# Sheet1.net
KiCad netlist of a schematic drawn in Altium Designer
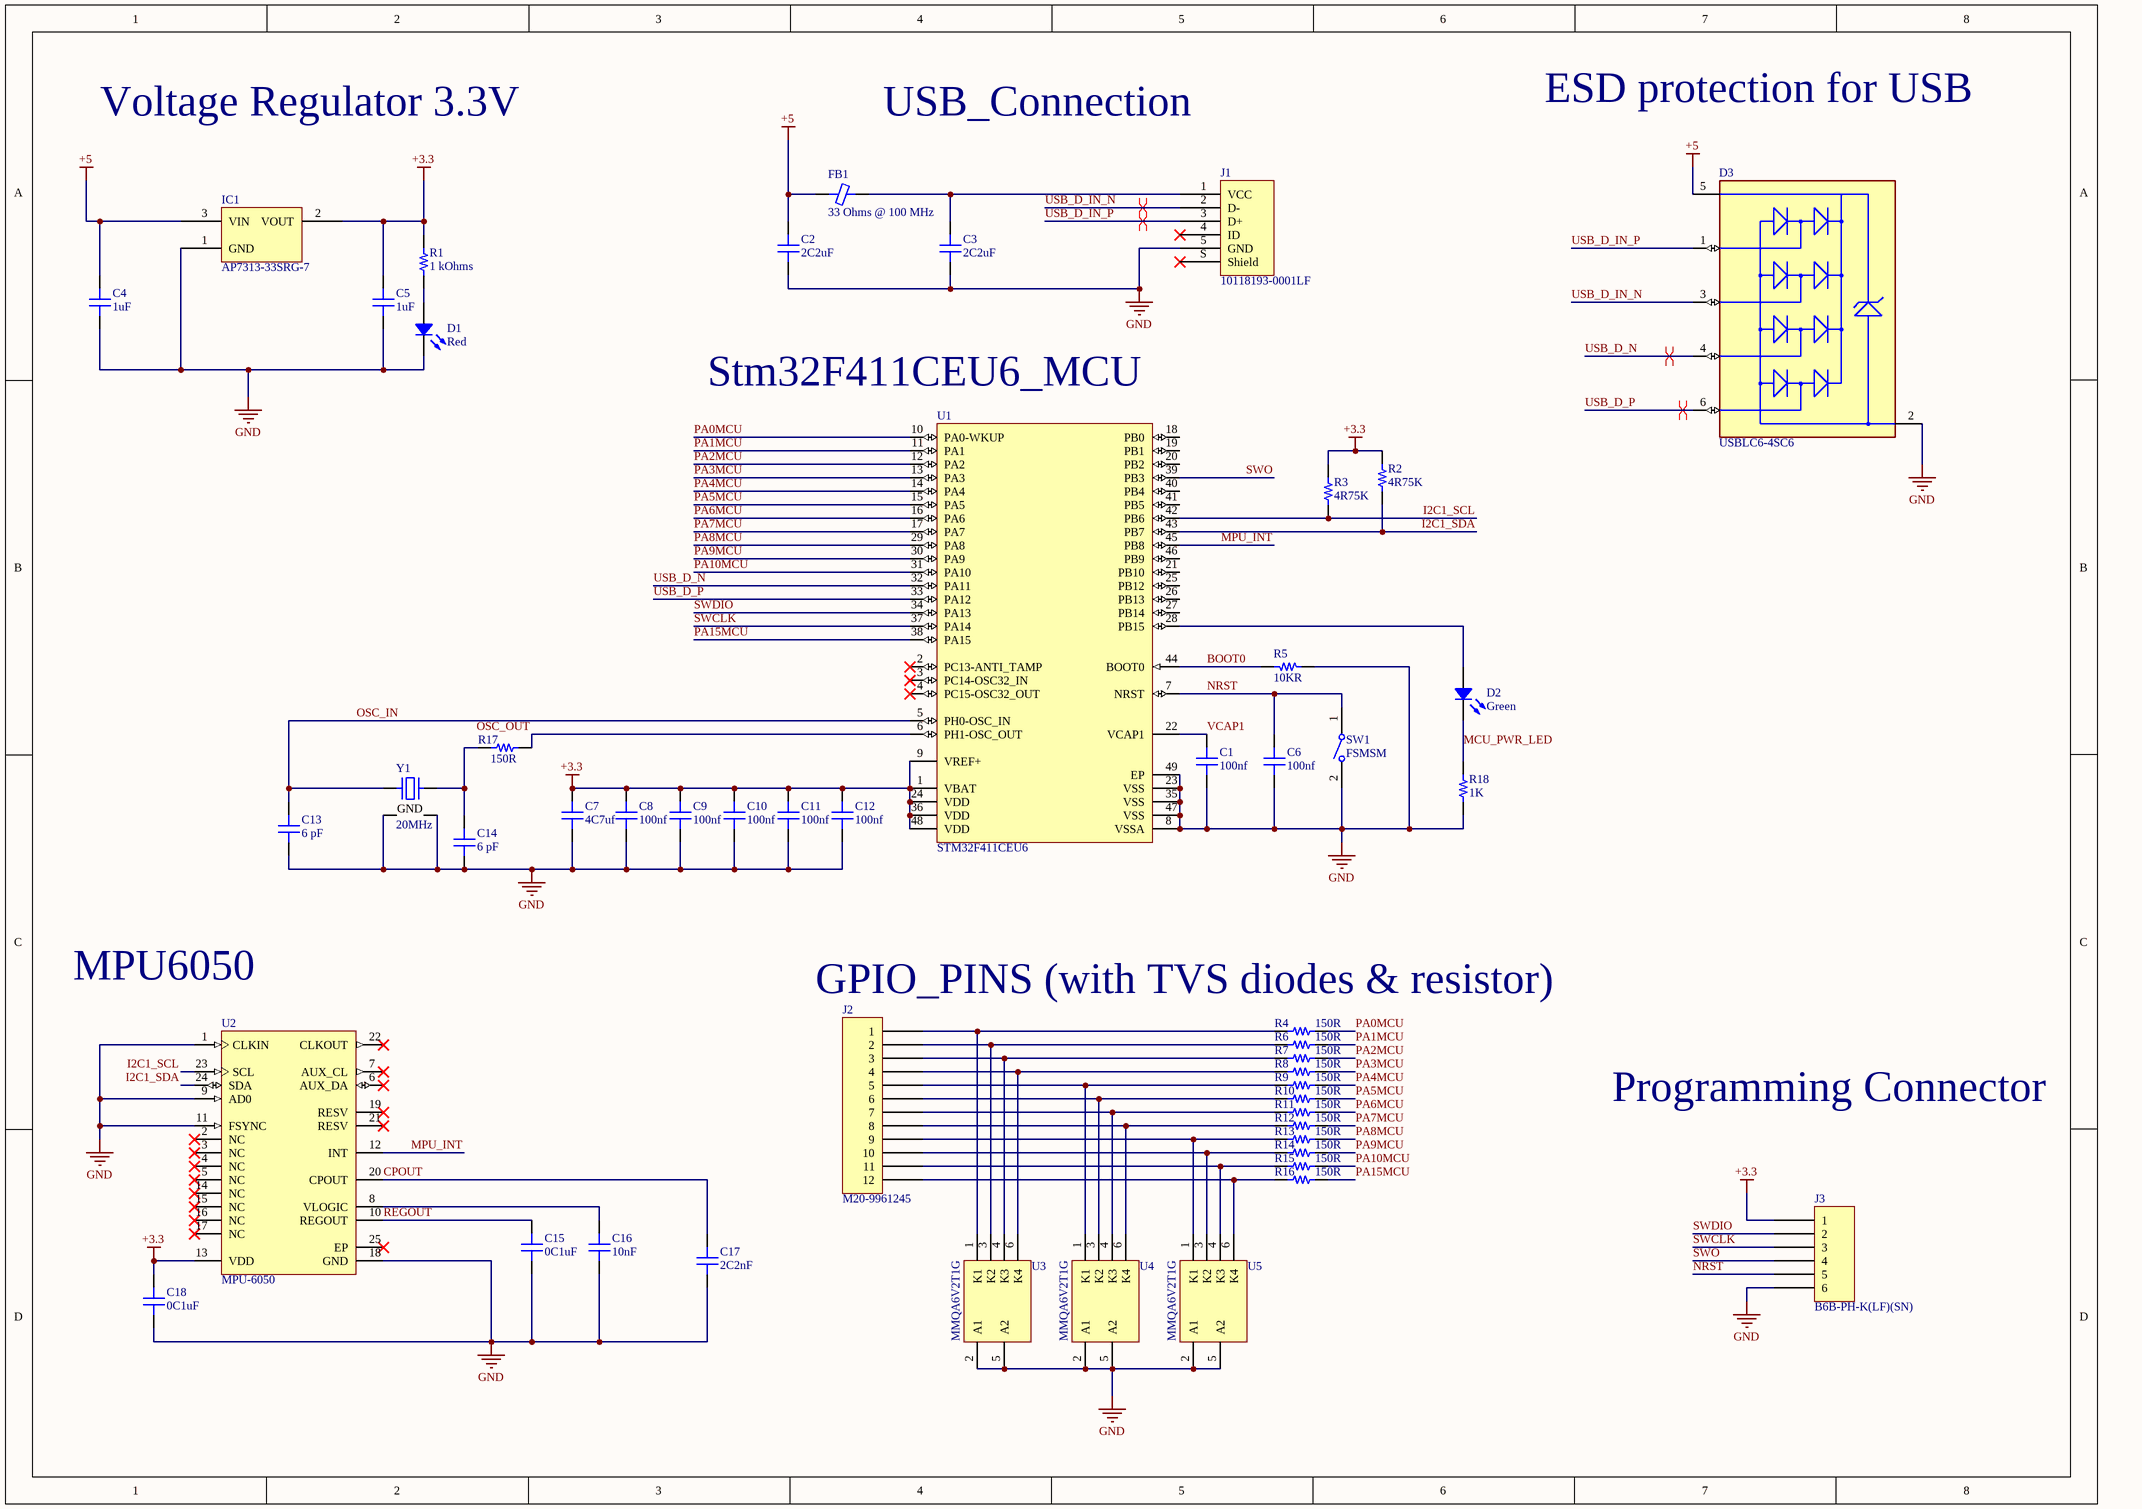
[diagram p0: Sheet1.SchDoc]

(export (version "E")
  (design (tool "Eeschema 10.0.6"))
  (components
    (comp (ref "C1")
      (value "100nf")
      (footprint "CAP 0603_1608")
      (description "CAP CER 0.1UF 6.3V X7R 0603")
      (fields
        (field (name "PART NUMBER") "6R3X14W104MV4T")
        (field (name "MANUFACTURER") "Johanson Dielectrics Inc.")
      )
      (libsource (lib "Celestial Altium Library - altium_library") (part "Capacitor"))
    )
    (comp (ref "C2")
      (value "2C2uF")
      (footprint "CAP 0805_2012")
      (description "CAP CER 2.2UF 16V X5R 0805")
      (fields (field (name "PART NUMBER") "EMK212BJ225KGHT") (field (name "MANUFACTURER") "Taiyo Yuden"))
      (libsource (lib "Celestial Altium Library - altium_library") (part "Capacitor"))
    )
    (comp (ref "C3")
      (value "2C2uF")
      (footprint "CAP 0805_2012")
      (description "CAP CER 2.2UF 16V X5R 0805")
      (fields (field (name "PART NUMBER") "EMK212BJ225KGHT") (field (name "MANUFACTURER") "Taiyo Yuden"))
      (libsource (lib "Celestial Altium Library - altium_library") (part "Capacitor"))
    )
    (comp (ref "C4")
      (value "1uF")
      (footprint "CAP 0805_2012")
      (description "CAP CER 0805 1UF 16V X7R 10%")
      (fields (field (name "PART NUMBER") "C0805C105K4RECAUTO") (field (name "MANUFACTURER") "KEMET"))
      (libsource (lib "Celestial Altium Library - altium_library") (part "Capacitor"))
    )
    (comp (ref "C5")
      (value "1uF")
      (footprint "CAP 0805_2012")
      (description "CAP CER 0805 1UF 16V X7R 10%")
      (fields (field (name "PART NUMBER") "C0805C105K4RECAUTO") (field (name "MANUFACTURER") "KEMET"))
      (libsource (lib "Celestial Altium Library - altium_library") (part "Capacitor"))
    )
    (comp (ref "C6")
      (value "100nf")
      (footprint "CAP 0603_1608")
      (description "CAP CER 0.1UF 6.3V X7R 0603")
      (fields
        (field (name "PART NUMBER") "6R3X14W104MV4T")
        (field (name "MANUFACTURER") "Johanson Dielectrics Inc.")
      )
      (libsource (lib "Celestial Altium Library - altium_library") (part "Capacitor"))
    )
    (comp (ref "C7")
      (value "4C7uf")
      (footprint "CAP 0603_1608")
      (description "CAP CER 4.7UF 6.3V X5R 0603")
      (fields (field (name "PART NUMBER") "06036D475KAT4A") (field (name "MANUFACTURER") "AVX Corporation"))
      (libsource (lib "Celestial Altium Library - altium_library") (part "Capacitor"))
    )
    (comp (ref "C8")
      (value "100nf")
      (footprint "CAP 0603_1608")
      (description "CAP CER 0.1UF 6.3V X7R 0603")
      (fields
        (field (name "PART NUMBER") "6R3X14W104MV4T")
        (field (name "MANUFACTURER") "Johanson Dielectrics Inc.")
      )
      (libsource (lib "Celestial Altium Library - altium_library") (part "Capacitor"))
    )
    (comp (ref "C9")
      (value "100nf")
      (footprint "CAP 0603_1608")
      (description "CAP CER 0.1UF 6.3V X7R 0603")
      (fields
        (field (name "PART NUMBER") "6R3X14W104MV4T")
        (field (name "MANUFACTURER") "Johanson Dielectrics Inc.")
      )
      (libsource (lib "Celestial Altium Library - altium_library") (part "Capacitor"))
    )
    (comp (ref "C10")
      (value "100nf")
      (footprint "CAP 0603_1608")
      (description "CAP CER 0.1UF 6.3V X7R 0603")
      (fields
        (field (name "PART NUMBER") "6R3X14W104MV4T")
        (field (name "MANUFACTURER") "Johanson Dielectrics Inc.")
      )
      (libsource (lib "Celestial Altium Library - altium_library") (part "Capacitor"))
    )
    (comp (ref "C11")
      (value "100nf")
      (footprint "CAP 0603_1608")
      (description "CAP CER 0.1UF 6.3V X7R 0603")
      (fields
        (field (name "PART NUMBER") "6R3X14W104MV4T")
        (field (name "MANUFACTURER") "Johanson Dielectrics Inc.")
      )
      (libsource (lib "Celestial Altium Library - altium_library") (part "Capacitor"))
    )
    (comp (ref "C12")
      (value "100nf")
      (footprint "CAP 0603_1608")
      (description "CAP CER 0.1UF 6.3V X7R 0603")
      (fields
        (field (name "PART NUMBER") "6R3X14W104MV4T")
        (field (name "MANUFACTURER") "Johanson Dielectrics Inc.")
      )
      (libsource (lib "Celestial Altium Library - altium_library") (part "Capacitor"))
    )
    (comp (ref "C13")
      (value "6 pF")
      (footprint "CAP 0805_2012")
      (description "CAP CER 6PF 50V C0G/NPO 0805")
      (fields (field (name "PART NUMBER") "CC0805CRNPO9BN6R0") (field (name "MANUFACTURER") "Yageo"))
      (libsource (lib "Celestial Altium Library - altium_library") (part "Capacitor"))
    )
    (comp (ref "C14")
      (value "6 pF")
      (footprint "CAP 0805_2012")
      (description "CAP CER 6PF 50V C0G/NPO 0805")
      (fields (field (name "PART NUMBER") "CC0805CRNPO9BN6R0") (field (name "MANUFACTURER") "Yageo"))
      (libsource (lib "Celestial Altium Library - altium_library") (part "Capacitor"))
    )
    (comp (ref "C15")
      (value "0C1uF")
      (footprint "CAP 0603_1608")
      (description "CAP CER 0.1UF 10V X7R 0603")
      (fields (field (name "PART NUMBER") "C0603X104K8RAC7867") (field (name "MANUFACTURER") "KEMET"))
      (libsource (lib "Celestial Altium Library - altium_library") (part "Capacitor"))
    )
    (comp (ref "C16")
      (value "10nF")
      (footprint "CAP 0805_2012")
      (description "CAP CER 10000PF 10V X7R 0805")
      (fields (field (name "PART NUMBER") "0805ZC103KAT2A") (field (name "MANUFACTURER") "AVX Corporation"))
      (libsource (lib "Celestial Altium Library - altium_library") (part "Capacitor"))
    )
    (comp (ref "C17")
      (value "2C2nF")
      (footprint "CAP 0603_1608")
      (description "CAP CER 2200PF 50V X7R 0603")
      (fields (field (name "PART NUMBER") "C0603X222K5RACAUTO") (field (name "MANUFACTURER") "KEMET"))
      (libsource (lib "Celestial Altium Library - altium_library") (part "Capacitor"))
    )
    (comp (ref "C18")
      (value "0C1uF")
      (footprint "CAP 0603_1608")
      (description "CAP CER 0.1UF 10V X7R 0603")
      (fields (field (name "PART NUMBER") "C0603X104K8RAC7867") (field (name "MANUFACTURER") "KEMET"))
      (libsource (lib "Celestial Altium Library - altium_library") (part "Capacitor"))
    )
    (comp (ref "D1")
      (value "Red")
      (footprint "LED 0603_1608 RED")
      (description "WL-SMCW SMT MONO-COLOR CHIP LED")
      (fields (field (name "PART NUMBER") "150060RS86000") (field (name "MANUFACTURER") "Würth Elektronik"))
      (libsource (lib "Celestial Altium Library - altium_library") (part "LED"))
    )
    (comp (ref "D2")
      (value "Green")
      (footprint "LED 0603_1608 GREEN")
      (description "WL-SMCW SMT MONO-COLOR CHIP LED")
      (fields (field (name "PART NUMBER") "150060VS75020") (field (name "MANUFACTURER") "Würth Elektronik"))
      (libsource (lib "Celestial Altium Library - altium_library") (part "LED"))
    )
    (comp (ref "D3")
      (value "USBLC6-4SC6")
      (footprint "FP-SOT23-6L-MFG")
      (description "TVS DIODE 5.25V 17V SOT23-6")
      (fields
        (field (name "MANUFACTURER") "STMicroelectronics")
        (field (name "OCTOPART") "https://octopart.com/usblc6-4sc6-stmicroelectronics-347147")
      )
      (libsource (lib "Altium Content Vault") (part "3e70b616ccdc4c88b528e1820c4a7da"))
    )
    (comp (ref "FB1")
      (value "33 Ohms @ 100 MHz")
      (footprint "FER 0201_0603")
      (description "FERRITE BEAD 33 OHM 0201 1LN")
      (fields (field (name "PART NUMBER") "MMZ0603F330CT000") (field (name "MANUFACTURER") "TDK Corporation"))
      (libsource (lib "Celestial Altium Library - altium_library") (part "Ferrite Chip"))
    )
    (comp (ref "IC1")
      (value "AP7313-33SRG-7")
      (footprint "DIODES SOT-23-3")
      (description "IC REG LIN 3.3V 150MA SOT23R-3")
      (fields (field (name "MANUFACTURER") "Diodes Incorporated"))
      (libsource (lib "Celestial Altium Library - altium_library") (part "Diodes Inc AP7313R"))
    )
    (comp (ref "J1")
      (value "10118193-0001LF")
      (footprint "FCI USB 10118193-0001LF")
      (description "CONN RCPT USB2.0 MICRO B SMD R/A")
      (fields (field (name "MANUFACTURER") "Amphenol ICC (FCI)"))
      (libsource (lib "Celestial Altium Library - altium_library") (part "USB 2.0 Type B Micro"))
    )
    (comp (ref "J2")
      (value "M20-9961245")
      (footprint "HARWIN M20-9961245")
      (description "CONN HEADER R/A 12POS 2.54MM")
      (fields (field (name "MANUFACTURER") "Harwin Inc."))
      (libsource (lib "Celestial Altium Library - altium_library") (part "12 Pin"))
    )
    (comp (ref "J3")
      (value "B6B-PH-K(LF)(SN)")
      (footprint "JST B6B-PH-K")
      (description "CONN HEADER VERT 6POS 2MM")
      (fields (field (name "MANUFACTURER") "JST Sales America Inc."))
      (libsource (lib "Celestial Altium Library - altium_library") (part "6 Pin"))
    )
    (comp (ref "R1")
      (value "1 kOhms")
      (footprint "RES 0805_2012")
      (description "3430 A2 1% 1K0 100PPM 1K RL")
      (fields
        (field (name "PART NUMBER") "3430A2F1K0TDF")
        (field (name "MANUFACTURER") "TE Connectivity Passive Product")
      )
      (libsource (lib "Celestial Altium Library - altium_library") (part "Resistor"))
    )
    (comp (ref "R2")
      (value "4R75K")
      (footprint "RES 0402_1005")
      (description "RES 4.75 KOHMS 0.1% 1/16W 0402")
      (fields
        (field (name "PART NUMBER") "RQ73C1E4K75BTD")
        (field (name "MANUFACTURER") "TE Connectivity Passive Product")
      )
      (libsource (lib "Celestial Altium Library - altium_library") (part "Resistor"))
    )
    (comp (ref "R3")
      (value "4R75K")
      (footprint "RES 0402_1005")
      (description "RES 4.75 KOHMS 0.1% 1/16W 0402")
      (fields
        (field (name "PART NUMBER") "RQ73C1E4K75BTD")
        (field (name "MANUFACTURER") "TE Connectivity Passive Product")
      )
      (libsource (lib "Celestial Altium Library - altium_library") (part "Resistor"))
    )
    (comp (ref "R4")
      (value "150R")
      (footprint "RES 0603_1608")
      (description "RA73F 1J 150R 0.1% 5K RL")
      (fields
        (field (name "PART NUMBER") "RA73F1J150RBTD")
        (field (name "MANUFACTURER") "TE Connectivity Passive Product")
      )
      (libsource (lib "Celestial Altium Library - altium_library") (part "Resistor"))
    )
    (comp (ref "R5")
      (value "10KR")
      (footprint "RES 0603_1608")
      (description "RES 10K OHM 0.5% 1/3W 0603")
      (fields
        (field (name "PART NUMBER") "SG73G1JTTD1002D")
        (field (name "MANUFACTURER") "KOA Speer Electronics, Inc.")
      )
      (libsource (lib "Celestial Altium Library - altium_library") (part "Resistor"))
    )
    (comp (ref "R6")
      (value "150R")
      (footprint "RES 0603_1608")
      (description "RA73F 1J 150R 0.1% 5K RL")
      (fields
        (field (name "PART NUMBER") "RA73F1J150RBTD")
        (field (name "MANUFACTURER") "TE Connectivity Passive Product")
      )
      (libsource (lib "Celestial Altium Library - altium_library") (part "Resistor"))
    )
    (comp (ref "R7")
      (value "150R")
      (footprint "RES 0603_1608")
      (description "RA73F 1J 150R 0.1% 5K RL")
      (fields
        (field (name "PART NUMBER") "RA73F1J150RBTD")
        (field (name "MANUFACTURER") "TE Connectivity Passive Product")
      )
      (libsource (lib "Celestial Altium Library - altium_library") (part "Resistor"))
    )
    (comp (ref "R8")
      (value "150R")
      (footprint "RES 0603_1608")
      (description "RA73F 1J 150R 0.1% 5K RL")
      (fields
        (field (name "PART NUMBER") "RA73F1J150RBTD")
        (field (name "MANUFACTURER") "TE Connectivity Passive Product")
      )
      (libsource (lib "Celestial Altium Library - altium_library") (part "Resistor"))
    )
    (comp (ref "R9")
      (value "150R")
      (footprint "RES 0603_1608")
      (description "RA73F 1J 150R 0.1% 5K RL")
      (fields
        (field (name "PART NUMBER") "RA73F1J150RBTD")
        (field (name "MANUFACTURER") "TE Connectivity Passive Product")
      )
      (libsource (lib "Celestial Altium Library - altium_library") (part "Resistor"))
    )
    (comp (ref "R10")
      (value "150R")
      (footprint "RES 0603_1608")
      (description "RA73F 1J 150R 0.1% 5K RL")
      (fields
        (field (name "PART NUMBER") "RA73F1J150RBTD")
        (field (name "MANUFACTURER") "TE Connectivity Passive Product")
      )
      (libsource (lib "Celestial Altium Library - altium_library") (part "Resistor"))
    )
    (comp (ref "R11")
      (value "150R")
      (footprint "RES 0603_1608")
      (description "RA73F 1J 150R 0.1% 5K RL")
      (fields
        (field (name "PART NUMBER") "RA73F1J150RBTD")
        (field (name "MANUFACTURER") "TE Connectivity Passive Product")
      )
      (libsource (lib "Celestial Altium Library - altium_library") (part "Resistor"))
    )
    (comp (ref "R12")
      (value "150R")
      (footprint "RES 0603_1608")
      (description "RA73F 1J 150R 0.1% 5K RL")
      (fields
        (field (name "PART NUMBER") "RA73F1J150RBTD")
        (field (name "MANUFACTURER") "TE Connectivity Passive Product")
      )
      (libsource (lib "Celestial Altium Library - altium_library") (part "Resistor"))
    )
    (comp (ref "R13")
      (value "150R")
      (footprint "RES 0603_1608")
      (description "RA73F 1J 150R 0.1% 5K RL")
      (fields
        (field (name "PART NUMBER") "RA73F1J150RBTD")
        (field (name "MANUFACTURER") "TE Connectivity Passive Product")
      )
      (libsource (lib "Celestial Altium Library - altium_library") (part "Resistor"))
    )
    (comp (ref "R14")
      (value "150R")
      (footprint "RES 0603_1608")
      (description "RA73F 1J 150R 0.1% 5K RL")
      (fields
        (field (name "PART NUMBER") "RA73F1J150RBTD")
        (field (name "MANUFACTURER") "TE Connectivity Passive Product")
      )
      (libsource (lib "Celestial Altium Library - altium_library") (part "Resistor"))
    )
    (comp (ref "R15")
      (value "150R")
      (footprint "RES 0603_1608")
      (description "RA73F 1J 150R 0.1% 5K RL")
      (fields
        (field (name "PART NUMBER") "RA73F1J150RBTD")
        (field (name "MANUFACTURER") "TE Connectivity Passive Product")
      )
      (libsource (lib "Celestial Altium Library - altium_library") (part "Resistor"))
    )
    (comp (ref "R16")
      (value "150R")
      (footprint "RES 0603_1608")
      (description "RA73F 1J 150R 0.1% 5K RL")
      (fields
        (field (name "PART NUMBER") "RA73F1J150RBTD")
        (field (name "MANUFACTURER") "TE Connectivity Passive Product")
      )
      (libsource (lib "Celestial Altium Library - altium_library") (part "Resistor"))
    )
    (comp (ref "R17")
      (value "150R")
      (footprint "RES 0402_1005")
      (description "RES 150 OHM 1% 1/4W 0402")
      (fields
        (field (name "PART NUMBER") "ERJ-PA2F1500X")
        (field (name "MANUFACTURER") "Panasonic Electronic Components")
      )
      (libsource (lib "Celestial Altium Library - altium_library") (part "Resistor"))
    )
    (comp (ref "R18")
      (value "1K")
      (footprint "RES 0402_1005")
      (description "0402 ANTI-SULFUR RES. , 0.5%, 1K")
      (fields
        (field (name "PART NUMBER") "ERJ-U02D1001X")
        (field (name "MANUFACTURER") "Panasonic Electronic Components")
      )
      (libsource (lib "Celestial Altium Library - altium_library") (part "Resistor"))
    )
    (comp (ref "SW1")
      (value "FSMSM")
      (footprint "TECO-FSMSM-2_V")
      (description "FSMSM Push Button Switch, 50 mA, -35 to 85 degC, 2-Pin SMD, RoHS, Bulk")
      (fields (field (name "MANUFACTURER") "TE Connectivity"))
      (libsource (lib "Altium Content Vault") (part "SW-SPST-2_C"))
    )
    (comp (ref "U1")
      (value "STM32F411CEU6")
      (footprint "STM-UFQFPN48_L")
      (libsource (lib "Altium Content Vault") (part "MC-ARM-STM32F411-UFQFPN48"))
    )
    (comp (ref "U2")
      (value "MPU-6050")
      (footprint "IS-QFN-24_V")
      (fields (field (name "MANUFACTURER") "InvenSense"))
      (libsource (lib "Altium Content Vault") (part "IS-MPU-6050-QFN-24"))
    )
    (comp (ref "U3")
      (value "MMQA6V2T1G")
      (footprint "ONSC-SC-74-6-318F-05_V")
      (fields (field (name "MANUFACTURER") "On Semiconductor"))
      (libsource (lib "Altium Content Vault") (part "ONSC-K1A2K3K4A5K6-6"))
    )
    (comp (ref "U4")
      (value "MMQA6V2T1G")
      (footprint "ONSC-SC-74-6-318F-05_V")
      (fields (field (name "MANUFACTURER") "On Semiconductor"))
      (libsource (lib "Altium Content Vault") (part "ONSC-K1A2K3K4A5K6-6"))
    )
    (comp (ref "U5")
      (value "MMQA6V2T1G")
      (footprint "ONSC-SC-74-6-318F-05_V")
      (fields (field (name "MANUFACTURER") "On Semiconductor"))
      (libsource (lib "Altium Content Vault") (part "ONSC-K1A2K3K4A5K6-6"))
    )
    (comp (ref "Y1")
      (value "20MHz")
      (footprint "KYOCERA CX2016DB")
      (description "CRYSTAL 20.0000MHZ 8PF SMD")
      (fields
        (field (name "PART NUMBER") "CX2016DB20000D0FLJCC")
        (field (name "MANUFACTURER") "Kyocera International Inc. Electronic Components")
      )
      (libsource (lib "Celestial Altium Library - altium_library") (part "Kyocera Crystal CX2016DB"))
    )
  )
  (nets
    (net (code "1") (name "+3.3") (class "Default")
      (node (ref "C10") (pin "1") (pinfunction "1_1") (pintype "passive"))
      (node (ref "C11") (pin "1") (pinfunction "1_1") (pintype "passive"))
      (node (ref "C12") (pin "1") (pinfunction "1_1") (pintype "passive"))
      (node (ref "C18") (pin "1") (pinfunction "1_1") (pintype "passive"))
      (node (ref "C5") (pin "1") (pinfunction "1_1") (pintype "passive"))
      (node (ref "C7") (pin "1") (pinfunction "1_1") (pintype "passive"))
      (node (ref "C8") (pin "1") (pinfunction "1_1") (pintype "passive"))
      (node (ref "C9") (pin "1") (pinfunction "1_1") (pintype "passive"))
      (node (ref "IC1") (pin "2") (pinfunction "VOUT_2") (pintype "passive"))
      (node (ref "J3") (pin "1") (pinfunction "1_1") (pintype "passive"))
      (node (ref "R1") (pin "1") (pinfunction "1_1") (pintype "passive"))
      (node (ref "R2") (pin "1") (pinfunction "1_1") (pintype "passive"))
      (node (ref "R3") (pin "1") (pinfunction "1_1") (pintype "passive"))
      (node (ref "U1") (pin "1") (pinfunction "VBAT_1") (pintype "power_in"))
      (node (ref "U1") (pin "24") (pinfunction "VDD_24") (pintype "power_in"))
      (node (ref "U1") (pin "36") (pinfunction "VDD_36") (pintype "power_in"))
      (node (ref "U1") (pin "48") (pinfunction "VDD_48") (pintype "power_in"))
      (node (ref "U1") (pin "9") (pinfunction "VREF+_9") (pintype "power_in"))
      (node (ref "U2") (pin "13") (pinfunction "VDD_13") (pintype "power_in"))
    )
    (net (code "2") (name "+5") (class "Default")
      (node (ref "C2") (pin "2") (pinfunction "2_2") (pintype "passive"))
      (node (ref "C4") (pin "1") (pinfunction "1_1") (pintype "passive"))
      (node (ref "D3") (pin "5") (pinfunction "VBUS_5") (pintype "power_in"))
      (node (ref "FB1") (pin "1") (pinfunction "1_1") (pintype "passive"))
      (node (ref "IC1") (pin "3") (pinfunction "VIN_3") (pintype "passive"))
    )
    (net (code "3") (name "/BOOT0") (class "Default")
      (node (ref "R5") (pin "2") (pinfunction "2_2") (pintype "passive"))
      (node (ref "U1") (pin "44") (pinfunction "BOOT0_44") (pintype "input"))
    )
    (net (code "4") (name "/CPOUT") (class "Default")
      (node (ref "C17") (pin "1") (pinfunction "1_1") (pintype "passive"))
      (node (ref "U2") (pin "20") (pinfunction "CPOUT_20") (pintype "passive"))
    )
    (net (code "5") (name "/I2C1_SCL") (class "Default")
      (node (ref "R3") (pin "2") (pinfunction "2_2") (pintype "passive"))
      (node (ref "U1") (pin "42") (pinfunction "PB6_42") (pintype "bidirectional"))
      (node (ref "U2") (pin "23") (pinfunction "SCL_23") (pintype "input"))
    )
    (net (code "6") (name "/I2C1_SDA") (class "Default")
      (node (ref "R2") (pin "2") (pinfunction "2_2") (pintype "passive"))
      (node (ref "U1") (pin "43") (pinfunction "PB7_43") (pintype "bidirectional"))
      (node (ref "U2") (pin "24") (pinfunction "SDA_24") (pintype "bidirectional"))
    )
    (net (code "7") (name "/MCU_PWR_LED") (class "Default")
      (node (ref "D2") (pin "2") (pinfunction "2_2") (pintype "passive"))
      (node (ref "R18") (pin "1") (pinfunction "1_1") (pintype "passive"))
    )
    (net (code "8") (name "/MPU_INT") (class "Default")
      (node (ref "U1") (pin "45") (pinfunction "PB8_45") (pintype "bidirectional"))
      (node (ref "U2") (pin "12") (pinfunction "INT_12") (pintype "open_collector"))
    )
    (net (code "9") (name "/NRST") (class "Default")
      (node (ref "C6") (pin "1") (pinfunction "1_1") (pintype "passive"))
      (node (ref "J3") (pin "5") (pinfunction "5_5") (pintype "passive"))
      (node (ref "SW1") (pin "1") (pinfunction "1_1") (pintype "passive"))
      (node (ref "U1") (pin "7") (pinfunction "NRST_7") (pintype "bidirectional"))
    )
    (net (code "10") (name "/OSC_IN") (class "Default")
      (node (ref "C13") (pin "1") (pinfunction "1_1") (pintype "passive"))
      (node (ref "U1") (pin "5") (pinfunction "PH0-OSC_IN_5") (pintype "bidirectional"))
      (node (ref "Y1") (pin "1") (pinfunction "1_1") (pintype "passive"))
    )
    (net (code "11") (name "/OSC_OUT") (class "Default")
      (node (ref "R17") (pin "2") (pinfunction "2_2") (pintype "passive"))
      (node (ref "U1") (pin "6") (pinfunction "PH1-OSC_OUT_6") (pintype "bidirectional"))
    )
    (net (code "12") (name "/PA0MCU") (class "Default")
      (node (ref "R4") (pin "2") (pinfunction "2_2") (pintype "passive"))
      (node (ref "U1") (pin "10") (pinfunction "PA0-WKUP_10") (pintype "bidirectional"))
    )
    (net (code "13") (name "/PA1MCU") (class "Default")
      (node (ref "R6") (pin "2") (pinfunction "2_2") (pintype "passive"))
      (node (ref "U1") (pin "11") (pinfunction "PA1_11") (pintype "bidirectional"))
    )
    (net (code "14") (name "/PA2MCU") (class "Default")
      (node (ref "R7") (pin "2") (pinfunction "2_2") (pintype "passive"))
      (node (ref "U1") (pin "12") (pinfunction "PA2_12") (pintype "bidirectional"))
    )
    (net (code "15") (name "/PA3MCU") (class "Default")
      (node (ref "R8") (pin "2") (pinfunction "2_2") (pintype "passive"))
      (node (ref "U1") (pin "13") (pinfunction "PA3_13") (pintype "bidirectional"))
    )
    (net (code "16") (name "/PA4MCU") (class "Default")
      (node (ref "R9") (pin "2") (pinfunction "2_2") (pintype "passive"))
      (node (ref "U1") (pin "14") (pinfunction "PA4_14") (pintype "bidirectional"))
    )
    (net (code "17") (name "/PA5MCU") (class "Default")
      (node (ref "R10") (pin "2") (pinfunction "2_2") (pintype "passive"))
      (node (ref "U1") (pin "15") (pinfunction "PA5_15") (pintype "bidirectional"))
    )
    (net (code "18") (name "/PA6MCU") (class "Default")
      (node (ref "R11") (pin "2") (pinfunction "2_2") (pintype "passive"))
      (node (ref "U1") (pin "16") (pinfunction "PA6_16") (pintype "bidirectional"))
    )
    (net (code "19") (name "/PA7MCU") (class "Default")
      (node (ref "R12") (pin "2") (pinfunction "2_2") (pintype "passive"))
      (node (ref "U1") (pin "17") (pinfunction "PA7_17") (pintype "bidirectional"))
    )
    (net (code "20") (name "/PA8MCU") (class "Default")
      (node (ref "R13") (pin "2") (pinfunction "2_2") (pintype "passive"))
      (node (ref "U1") (pin "29") (pinfunction "PA8_29") (pintype "bidirectional"))
    )
    (net (code "21") (name "/PA9MCU") (class "Default")
      (node (ref "R14") (pin "2") (pinfunction "2_2") (pintype "passive"))
      (node (ref "U1") (pin "30") (pinfunction "PA9_30") (pintype "bidirectional"))
    )
    (net (code "22") (name "/PA10MCU") (class "Default")
      (node (ref "R15") (pin "2") (pinfunction "2_2") (pintype "passive"))
      (node (ref "U1") (pin "31") (pinfunction "PA10_31") (pintype "bidirectional"))
    )
    (net (code "23") (name "/PA15MCU") (class "Default")
      (node (ref "R16") (pin "2") (pinfunction "2_2") (pintype "passive"))
      (node (ref "U1") (pin "38") (pinfunction "PA15_38") (pintype "bidirectional"))
    )
    (net (code "24") (name "/REGOUT") (class "Default")
      (node (ref "C15") (pin "1") (pinfunction "1_1") (pintype "passive"))
      (node (ref "U2") (pin "10") (pinfunction "REGOUT_10") (pintype "passive"))
    )
    (net (code "25") (name "/SWCLK") (class "Default")
      (node (ref "J3") (pin "3") (pinfunction "3_3") (pintype "passive"))
      (node (ref "U1") (pin "37") (pinfunction "PA14_37") (pintype "bidirectional"))
    )
    (net (code "26") (name "/SWDIO") (class "Default")
      (node (ref "J3") (pin "2") (pinfunction "2_2") (pintype "passive"))
      (node (ref "U1") (pin "34") (pinfunction "PA13_34") (pintype "bidirectional"))
    )
    (net (code "27") (name "/SWO") (class "Default")
      (node (ref "J3") (pin "4") (pinfunction "4_4") (pintype "passive"))
      (node (ref "U1") (pin "39") (pinfunction "PB3_39") (pintype "bidirectional"))
    )
    (net (code "28") (name "/USB_D_IN_N") (class "Default")
      (node (ref "D3") (pin "3") (pinfunction "I/O2_3") (pintype "bidirectional"))
      (node (ref "J1") (pin "2") (pinfunction "D-_2") (pintype "passive"))
    )
    (net (code "29") (name "/USB_D_IN_P") (class "Default")
      (node (ref "D3") (pin "1") (pinfunction "I/O1_1") (pintype "bidirectional"))
      (node (ref "J1") (pin "3") (pinfunction "D+_3") (pintype "passive"))
    )
    (net (code "30") (name "/USB_D_N") (class "Default")
      (node (ref "D3") (pin "4") (pinfunction "I/O3_4") (pintype "bidirectional"))
      (node (ref "U1") (pin "32") (pinfunction "PA11_32") (pintype "bidirectional"))
    )
    (net (code "31") (name "/USB_D_P") (class "Default")
      (node (ref "D3") (pin "6") (pinfunction "I/O4_6") (pintype "bidirectional"))
      (node (ref "U1") (pin "33") (pinfunction "PA12_33") (pintype "bidirectional"))
    )
    (net (code "32") (name "/VCAP1") (class "Default")
      (node (ref "C1") (pin "1") (pinfunction "1_1") (pintype "passive"))
      (node (ref "U1") (pin "22") (pinfunction "VCAP1_22") (pintype "passive"))
    )
    (net (code "33") (name "GND") (class "Default")
      (node (ref "C1") (pin "2") (pinfunction "2_2") (pintype "passive"))
      (node (ref "C10") (pin "2") (pinfunction "2_2") (pintype "passive"))
      (node (ref "C11") (pin "2") (pinfunction "2_2") (pintype "passive"))
      (node (ref "C12") (pin "2") (pinfunction "2_2") (pintype "passive"))
      (node (ref "C13") (pin "2") (pinfunction "2_2") (pintype "passive"))
      (node (ref "C14") (pin "2") (pinfunction "2_2") (pintype "passive"))
      (node (ref "C15") (pin "2") (pinfunction "2_2") (pintype "passive"))
      (node (ref "C16") (pin "2") (pinfunction "2_2") (pintype "passive"))
      (node (ref "C17") (pin "2") (pinfunction "2_2") (pintype "passive"))
      (node (ref "C18") (pin "2") (pinfunction "2_2") (pintype "passive"))
      (node (ref "C2") (pin "1") (pinfunction "1_1") (pintype "passive"))
      (node (ref "C3") (pin "1") (pinfunction "1_1") (pintype "passive"))
      (node (ref "C4") (pin "2") (pinfunction "2_2") (pintype "passive"))
      (node (ref "C5") (pin "2") (pinfunction "2_2") (pintype "passive"))
      (node (ref "C6") (pin "2") (pinfunction "2_2") (pintype "passive"))
      (node (ref "C7") (pin "2") (pinfunction "2_2") (pintype "passive"))
      (node (ref "C8") (pin "2") (pinfunction "2_2") (pintype "passive"))
      (node (ref "C9") (pin "2") (pinfunction "2_2") (pintype "passive"))
      (node (ref "D1") (pin "2") (pinfunction "2_2") (pintype "passive"))
      (node (ref "D3") (pin "2") (pinfunction "GND_2") (pintype "power_in"))
      (node (ref "IC1") (pin "1") (pinfunction "GND_1") (pintype "passive"))
      (node (ref "J1") (pin "5") (pinfunction "GND_5") (pintype "passive"))
      (node (ref "J3") (pin "6") (pinfunction "6_6") (pintype "passive"))
      (node (ref "R18") (pin "2") (pinfunction "2_2") (pintype "passive"))
      (node (ref "R5") (pin "1") (pinfunction "1_1") (pintype "passive"))
      (node (ref "SW1") (pin "2") (pinfunction "2_2") (pintype "passive"))
      (node (ref "U1") (pin "23") (pinfunction "VSS_23") (pintype "power_in"))
      (node (ref "U1") (pin "35") (pinfunction "VSS_35") (pintype "power_in"))
      (node (ref "U1") (pin "47") (pinfunction "VSS_47") (pintype "power_in"))
      (node (ref "U1") (pin "49") (pinfunction "EP_49") (pintype "power_in"))
      (node (ref "U1") (pin "8") (pinfunction "VSSA_8") (pintype "power_in"))
      (node (ref "U2") (pin "1") (pinfunction "CLKIN_1") (pintype "input"))
      (node (ref "U2") (pin "11") (pinfunction "FSYNC_11") (pintype "input"))
      (node (ref "U2") (pin "18") (pinfunction "GND_18") (pintype "power_in"))
      (node (ref "U2") (pin "9") (pinfunction "AD0_9") (pintype "input"))
      (node (ref "U3") (pin "2") (pinfunction "A1_2") (pintype "passive"))
      (node (ref "U3") (pin "5") (pinfunction "A2_5") (pintype "passive"))
      (node (ref "U4") (pin "2") (pinfunction "A1_2") (pintype "passive"))
      (node (ref "U4") (pin "5") (pinfunction "A2_5") (pintype "passive"))
      (node (ref "U5") (pin "2") (pinfunction "A1_2") (pintype "passive"))
      (node (ref "U5") (pin "5") (pinfunction "A2_5") (pintype "passive"))
      (node (ref "Y1") (pin "2") (pinfunction "GND_2") (pintype "passive"))
      (node (ref "Y1") (pin "4") (pinfunction "GND_4") (pintype "passive"))
    )
    (net (code "34") (name "Net-(C14-Pad1)") (class "Default")
      (node (ref "C14") (pin "1") (pinfunction "1_1") (pintype "passive"))
      (node (ref "R17") (pin "1") (pinfunction "1_1") (pintype "passive"))
      (node (ref "Y1") (pin "3") (pinfunction "3_3") (pintype "passive"))
    )
    (net (code "35") (name "Net-(D1-Pad1)") (class "Default")
      (node (ref "D1") (pin "1") (pinfunction "1_1") (pintype "passive"))
      (node (ref "R1") (pin "2") (pinfunction "2_2") (pintype "passive"))
    )
    (net (code "36") (name "Net-(J1-VCC)") (class "Default")
      (node (ref "C3") (pin "2") (pinfunction "2_2") (pintype "passive"))
      (node (ref "FB1") (pin "2") (pinfunction "2_2") (pintype "passive"))
      (node (ref "J1") (pin "1") (pinfunction "VCC_1") (pintype "passive"))
    )
    (net (code "37") (name "Net-(U1-PB15)") (class "Default")
      (node (ref "D2") (pin "1") (pinfunction "1_1") (pintype "passive"))
      (node (ref "U1") (pin "28") (pinfunction "PB15_28") (pintype "bidirectional"))
    )
    (net (code "38") (name "Net-(U2-VLOGIC)") (class "Default")
      (node (ref "C16") (pin "1") (pinfunction "1_1") (pintype "passive"))
      (node (ref "U2") (pin "8") (pinfunction "VLOGIC_8") (pintype "power_in"))
    )
    (net (code "39") (name "Net-(U3-K1)") (class "Default")
      (node (ref "J2") (pin "1") (pinfunction "1_1") (pintype "passive"))
      (node (ref "R4") (pin "1") (pinfunction "1_1") (pintype "passive"))
      (node (ref "U3") (pin "1") (pinfunction "K1_1") (pintype "passive"))
    )
    (net (code "40") (name "Net-(U3-K2)") (class "Default")
      (node (ref "J2") (pin "2") (pinfunction "2_2") (pintype "passive"))
      (node (ref "R6") (pin "1") (pinfunction "1_1") (pintype "passive"))
      (node (ref "U3") (pin "3") (pinfunction "K2_3") (pintype "passive"))
    )
    (net (code "41") (name "Net-(U3-K3)") (class "Default")
      (node (ref "J2") (pin "3") (pinfunction "3_3") (pintype "passive"))
      (node (ref "R7") (pin "1") (pinfunction "1_1") (pintype "passive"))
      (node (ref "U3") (pin "4") (pinfunction "K3_4") (pintype "passive"))
    )
    (net (code "42") (name "Net-(U3-K4)") (class "Default")
      (node (ref "J2") (pin "4") (pinfunction "4_4") (pintype "passive"))
      (node (ref "R8") (pin "1") (pinfunction "1_1") (pintype "passive"))
      (node (ref "U3") (pin "6") (pinfunction "K4_6") (pintype "passive"))
    )
    (net (code "43") (name "Net-(U4-K1)") (class "Default")
      (node (ref "J2") (pin "5") (pinfunction "5_5") (pintype "passive"))
      (node (ref "R9") (pin "1") (pinfunction "1_1") (pintype "passive"))
      (node (ref "U4") (pin "1") (pinfunction "K1_1") (pintype "passive"))
    )
    (net (code "44") (name "Net-(U4-K2)") (class "Default")
      (node (ref "J2") (pin "6") (pinfunction "6_6") (pintype "passive"))
      (node (ref "R10") (pin "1") (pinfunction "1_1") (pintype "passive"))
      (node (ref "U4") (pin "3") (pinfunction "K2_3") (pintype "passive"))
    )
    (net (code "45") (name "Net-(U4-K3)") (class "Default")
      (node (ref "J2") (pin "7") (pinfunction "7_7") (pintype "passive"))
      (node (ref "R11") (pin "1") (pinfunction "1_1") (pintype "passive"))
      (node (ref "U4") (pin "4") (pinfunction "K3_4") (pintype "passive"))
    )
    (net (code "46") (name "Net-(U4-K4)") (class "Default")
      (node (ref "J2") (pin "8") (pinfunction "8_8") (pintype "passive"))
      (node (ref "R12") (pin "1") (pinfunction "1_1") (pintype "passive"))
      (node (ref "U4") (pin "6") (pinfunction "K4_6") (pintype "passive"))
    )
    (net (code "47") (name "Net-(U5-K1)") (class "Default")
      (node (ref "J2") (pin "9") (pinfunction "9_9") (pintype "passive"))
      (node (ref "R13") (pin "1") (pinfunction "1_1") (pintype "passive"))
      (node (ref "U5") (pin "1") (pinfunction "K1_1") (pintype "passive"))
    )
    (net (code "48") (name "Net-(U5-K2)") (class "Default")
      (node (ref "J2") (pin "10") (pinfunction "10_10") (pintype "passive"))
      (node (ref "R14") (pin "1") (pinfunction "1_1") (pintype "passive"))
      (node (ref "U5") (pin "3") (pinfunction "K2_3") (pintype "passive"))
    )
    (net (code "49") (name "Net-(U5-K3)") (class "Default")
      (node (ref "J2") (pin "11") (pinfunction "11_11") (pintype "passive"))
      (node (ref "R15") (pin "1") (pinfunction "1_1") (pintype "passive"))
      (node (ref "U5") (pin "4") (pinfunction "K3_4") (pintype "passive"))
    )
    (net (code "50") (name "Net-(U5-K4)") (class "Default")
      (node (ref "J2") (pin "12") (pinfunction "12_12") (pintype "passive"))
      (node (ref "R16") (pin "1") (pinfunction "1_1") (pintype "passive"))
      (node (ref "U5") (pin "6") (pinfunction "K4_6") (pintype "passive"))
    )
    (net (code "51") (name "unconnected-(J1-ID-Pad4)") (class "Default")
      (node (ref "J1") (pin "4") (pinfunction "ID_4") (pintype "passive+no_connect"))
    )
    (net (code "52") (name "unconnected-(J1-Shield-PadS)") (class "Default")
      (node (ref "J1") (pin "S") (pinfunction "Shield_S") (pintype "passive+no_connect"))
    )
    (net (code "53") (name "unconnected-(U1-PB0-Pad18)") (class "Default")
      (node (ref "U1") (pin "18") (pinfunction "PB0_18") (pintype "bidirectional"))
    )
    (net (code "54") (name "unconnected-(U1-PB1-Pad19)") (class "Default")
      (node (ref "U1") (pin "19") (pinfunction "PB1_19") (pintype "bidirectional"))
    )
    (net (code "55") (name "unconnected-(U1-PB2-Pad20)") (class "Default")
      (node (ref "U1") (pin "20") (pinfunction "PB2_20") (pintype "bidirectional"))
    )
    (net (code "56") (name "unconnected-(U1-PB4-Pad40)") (class "Default")
      (node (ref "U1") (pin "40") (pinfunction "PB4_40") (pintype "bidirectional"))
    )
    (net (code "57") (name "unconnected-(U1-PB5-Pad41)") (class "Default")
      (node (ref "U1") (pin "41") (pinfunction "PB5_41") (pintype "bidirectional"))
    )
    (net (code "58") (name "unconnected-(U1-PB9-Pad46)") (class "Default")
      (node (ref "U1") (pin "46") (pinfunction "PB9_46") (pintype "bidirectional"))
    )
    (net (code "59") (name "unconnected-(U1-PB10-Pad21)") (class "Default")
      (node (ref "U1") (pin "21") (pinfunction "PB10_21") (pintype "bidirectional"))
    )
    (net (code "60") (name "unconnected-(U1-PB12-Pad25)") (class "Default")
      (node (ref "U1") (pin "25") (pinfunction "PB12_25") (pintype "bidirectional"))
    )
    (net (code "61") (name "unconnected-(U1-PB13-Pad26)") (class "Default")
      (node (ref "U1") (pin "26") (pinfunction "PB13_26") (pintype "bidirectional"))
    )
    (net (code "62") (name "unconnected-(U1-PB14-Pad27)") (class "Default")
      (node (ref "U1") (pin "27") (pinfunction "PB14_27") (pintype "bidirectional"))
    )
    (net (code "63") (name "unconnected-(U1-PC13-ANTI_TAMP-Pad2)") (class "Default")
      (node (ref "U1") (pin "2") (pinfunction "PC13-ANTI_TAMP_2") (pintype "bidirectional+no_connect"))
    )
    (net (code "64") (name "unconnected-(U1-PC14-OSC32_IN-Pad3)") (class "Default")
      (node (ref "U1") (pin "3") (pinfunction "PC14-OSC32_IN_3") (pintype "bidirectional+no_connect"))
    )
    (net (code "65") (name "unconnected-(U1-PC15-OSC32_OUT-Pad4)") (class "Default")
      (node (ref "U1") (pin "4") (pinfunction "PC15-OSC32_OUT_4") (pintype "bidirectional+no_connect"))
    )
    (net (code "66") (name "unconnected-(U2-AUX_CL-Pad7)") (class "Default")
      (node (ref "U2") (pin "7") (pinfunction "AUX_CL_7") (pintype "output+no_connect"))
    )
    (net (code "67") (name "unconnected-(U2-AUX_DA-Pad6)") (class "Default")
      (node (ref "U2") (pin "6") (pinfunction "AUX_DA_6") (pintype "bidirectional+no_connect"))
    )
    (net (code "68") (name "unconnected-(U2-CLKOUT-Pad22)") (class "Default")
      (node (ref "U2") (pin "22") (pinfunction "CLKOUT_22") (pintype "output+no_connect"))
    )
    (net (code "69") (name "unconnected-(U2-EP-Pad25)") (class "Default")
      (node (ref "U2") (pin "25") (pinfunction "EP_25") (pintype "power_in+no_connect"))
    )
    (net (code "70") (name "unconnected-(U2-NC-Pad2)") (class "Default")
      (node (ref "U2") (pin "2") (pinfunction "NC_2") (pintype "passive+no_connect"))
    )
    (net (code "71") (name "unconnected-(U2-NC-Pad3)") (class "Default")
      (node (ref "U2") (pin "3") (pinfunction "NC_3") (pintype "passive+no_connect"))
    )
    (net (code "72") (name "unconnected-(U2-NC-Pad4)") (class "Default")
      (node (ref "U2") (pin "4") (pinfunction "NC_4") (pintype "passive+no_connect"))
    )
    (net (code "73") (name "unconnected-(U2-NC-Pad5)") (class "Default")
      (node (ref "U2") (pin "5") (pinfunction "NC_5") (pintype "passive+no_connect"))
    )
    (net (code "74") (name "unconnected-(U2-NC-Pad14)") (class "Default")
      (node (ref "U2") (pin "14") (pinfunction "NC_14") (pintype "passive+no_connect"))
    )
    (net (code "75") (name "unconnected-(U2-NC-Pad15)") (class "Default")
      (node (ref "U2") (pin "15") (pinfunction "NC_15") (pintype "passive+no_connect"))
    )
    (net (code "76") (name "unconnected-(U2-NC-Pad16)") (class "Default")
      (node (ref "U2") (pin "16") (pinfunction "NC_16") (pintype "passive+no_connect"))
    )
    (net (code "77") (name "unconnected-(U2-NC-Pad17)") (class "Default")
      (node (ref "U2") (pin "17") (pinfunction "NC_17") (pintype "passive+no_connect"))
    )
    (net (code "78") (name "unconnected-(U2-RESV-Pad19)") (class "Default")
      (node (ref "U2") (pin "19") (pinfunction "RESV_19") (pintype "passive+no_connect"))
    )
    (net (code "79") (name "unconnected-(U2-RESV-Pad21)") (class "Default")
      (node (ref "U2") (pin "21") (pinfunction "RESV_21") (pintype "passive+no_connect"))
    )
  )
)
